# ProDocument_FAB-O-MATIC_2024-05-19.net
KiCad netlist of a schematic drawn in EasyEDA Pro
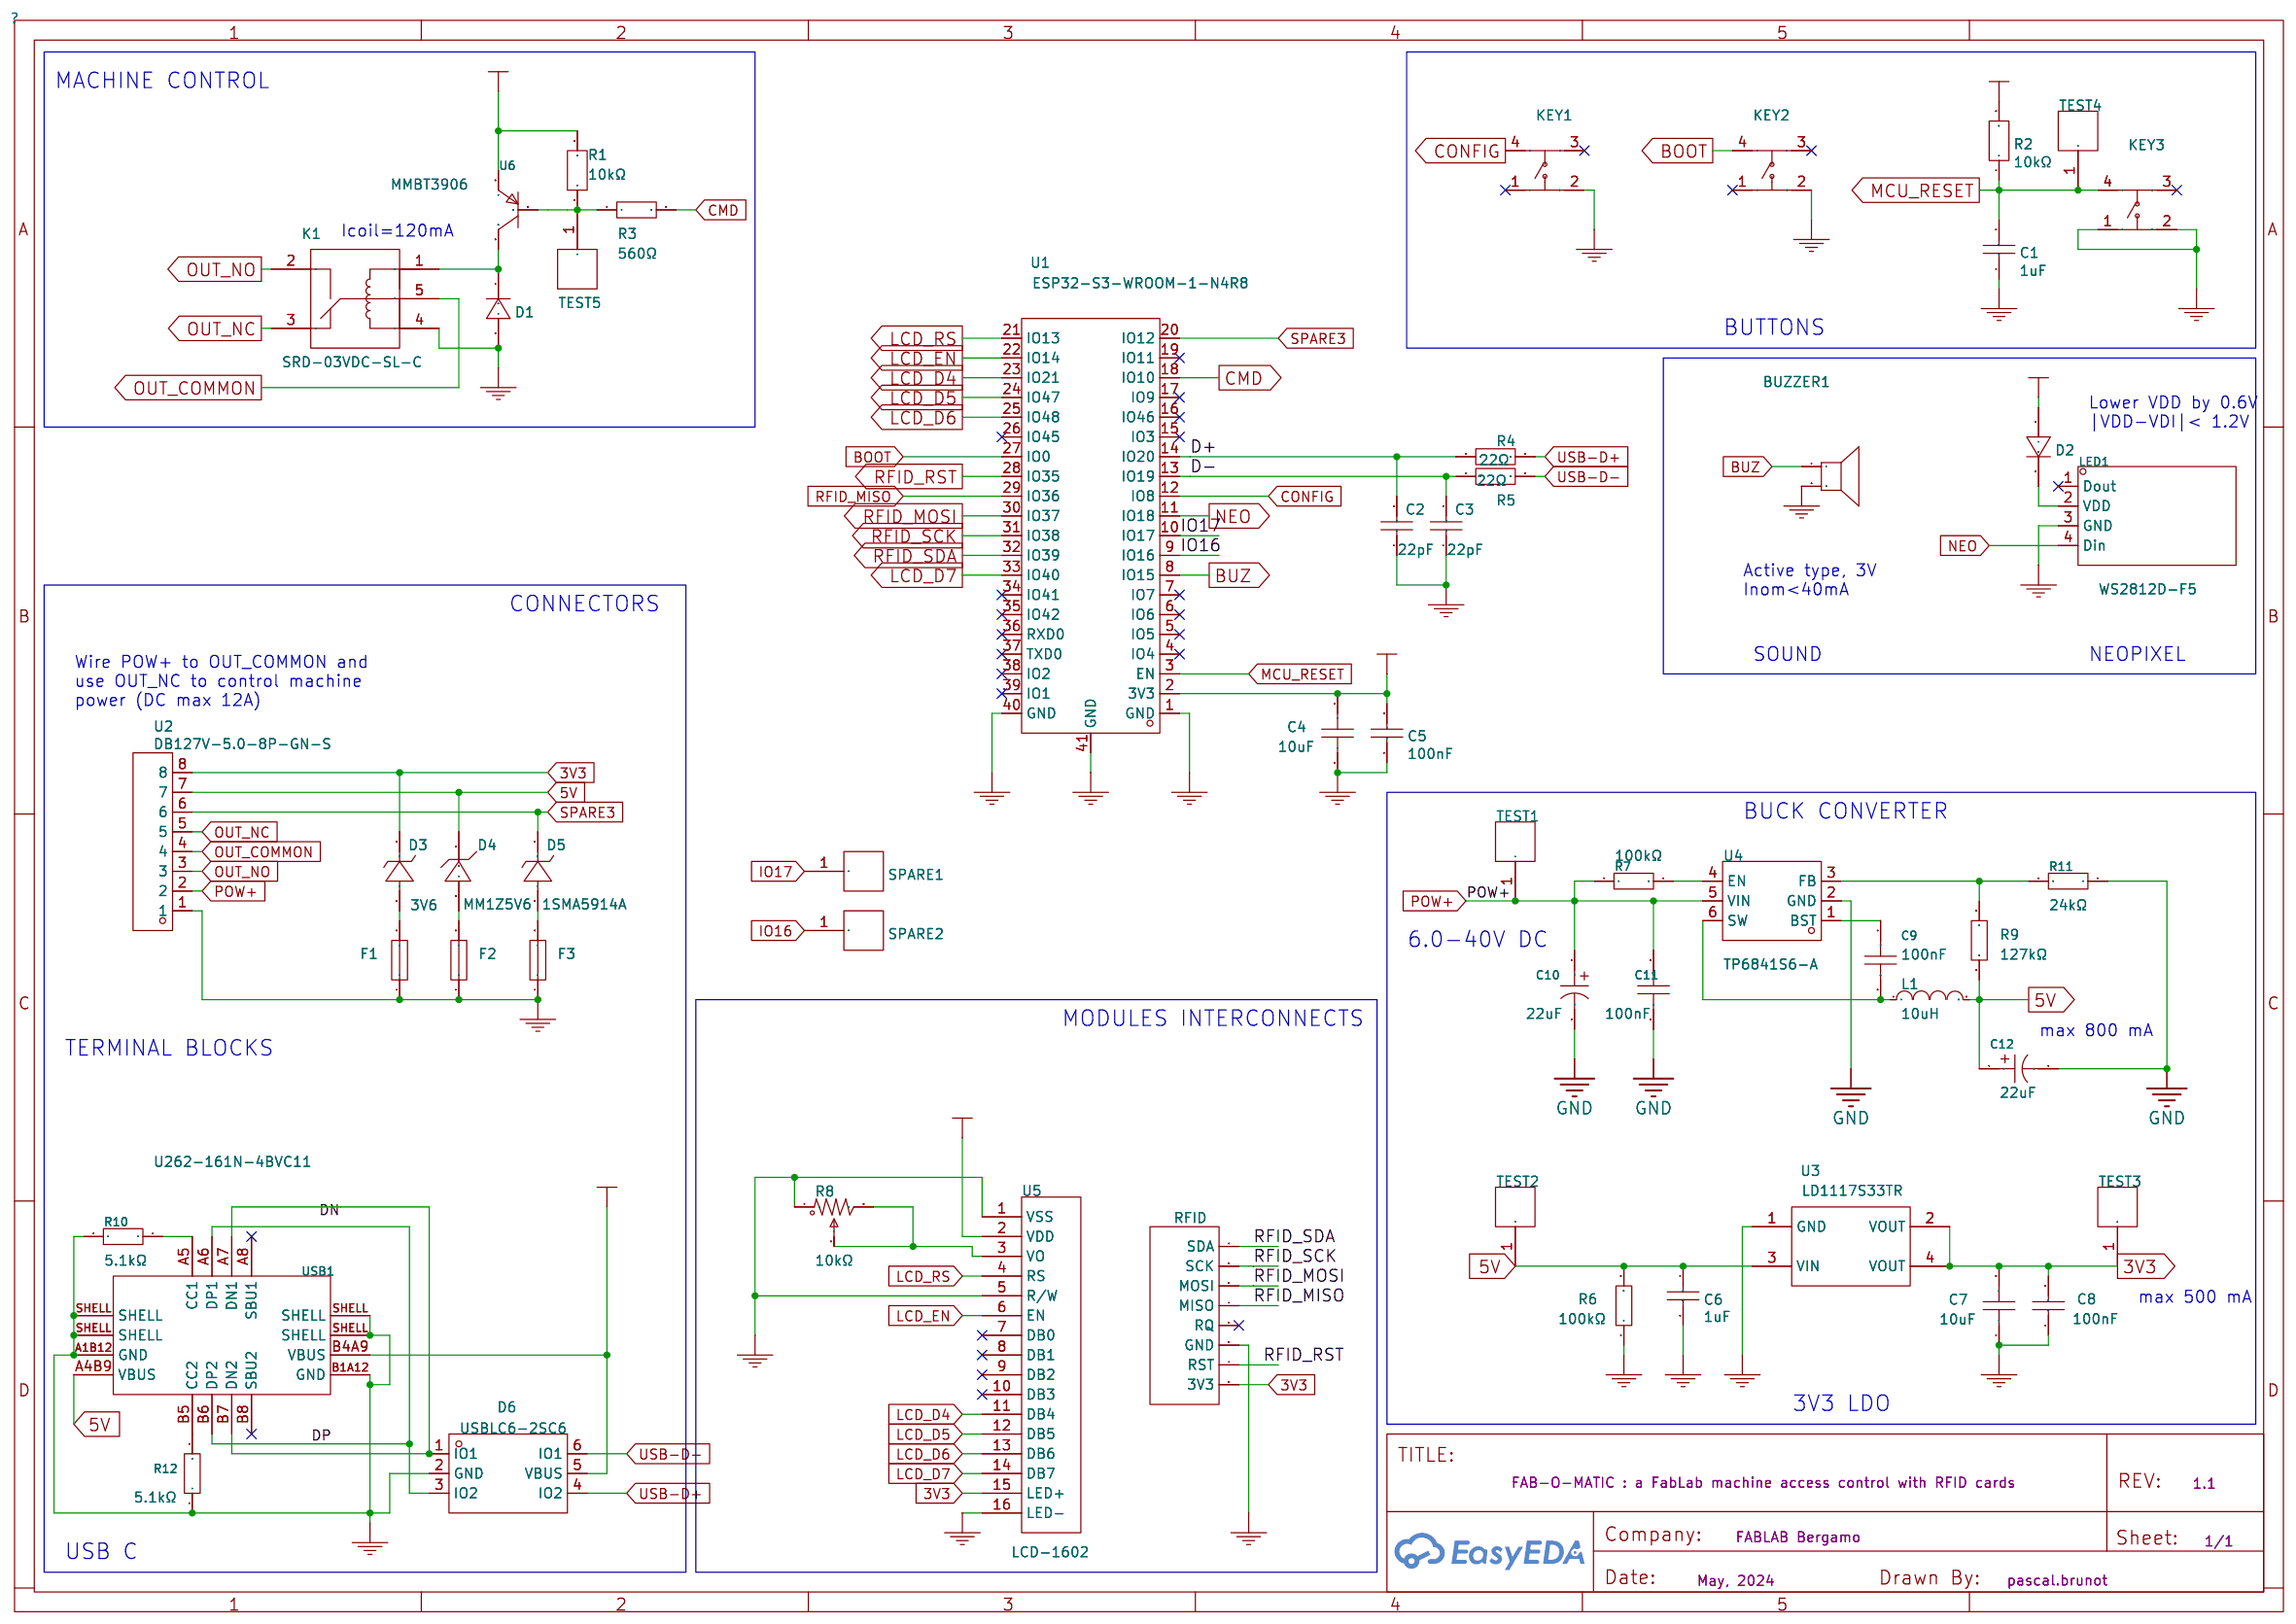
[diagram p0: Schematics]
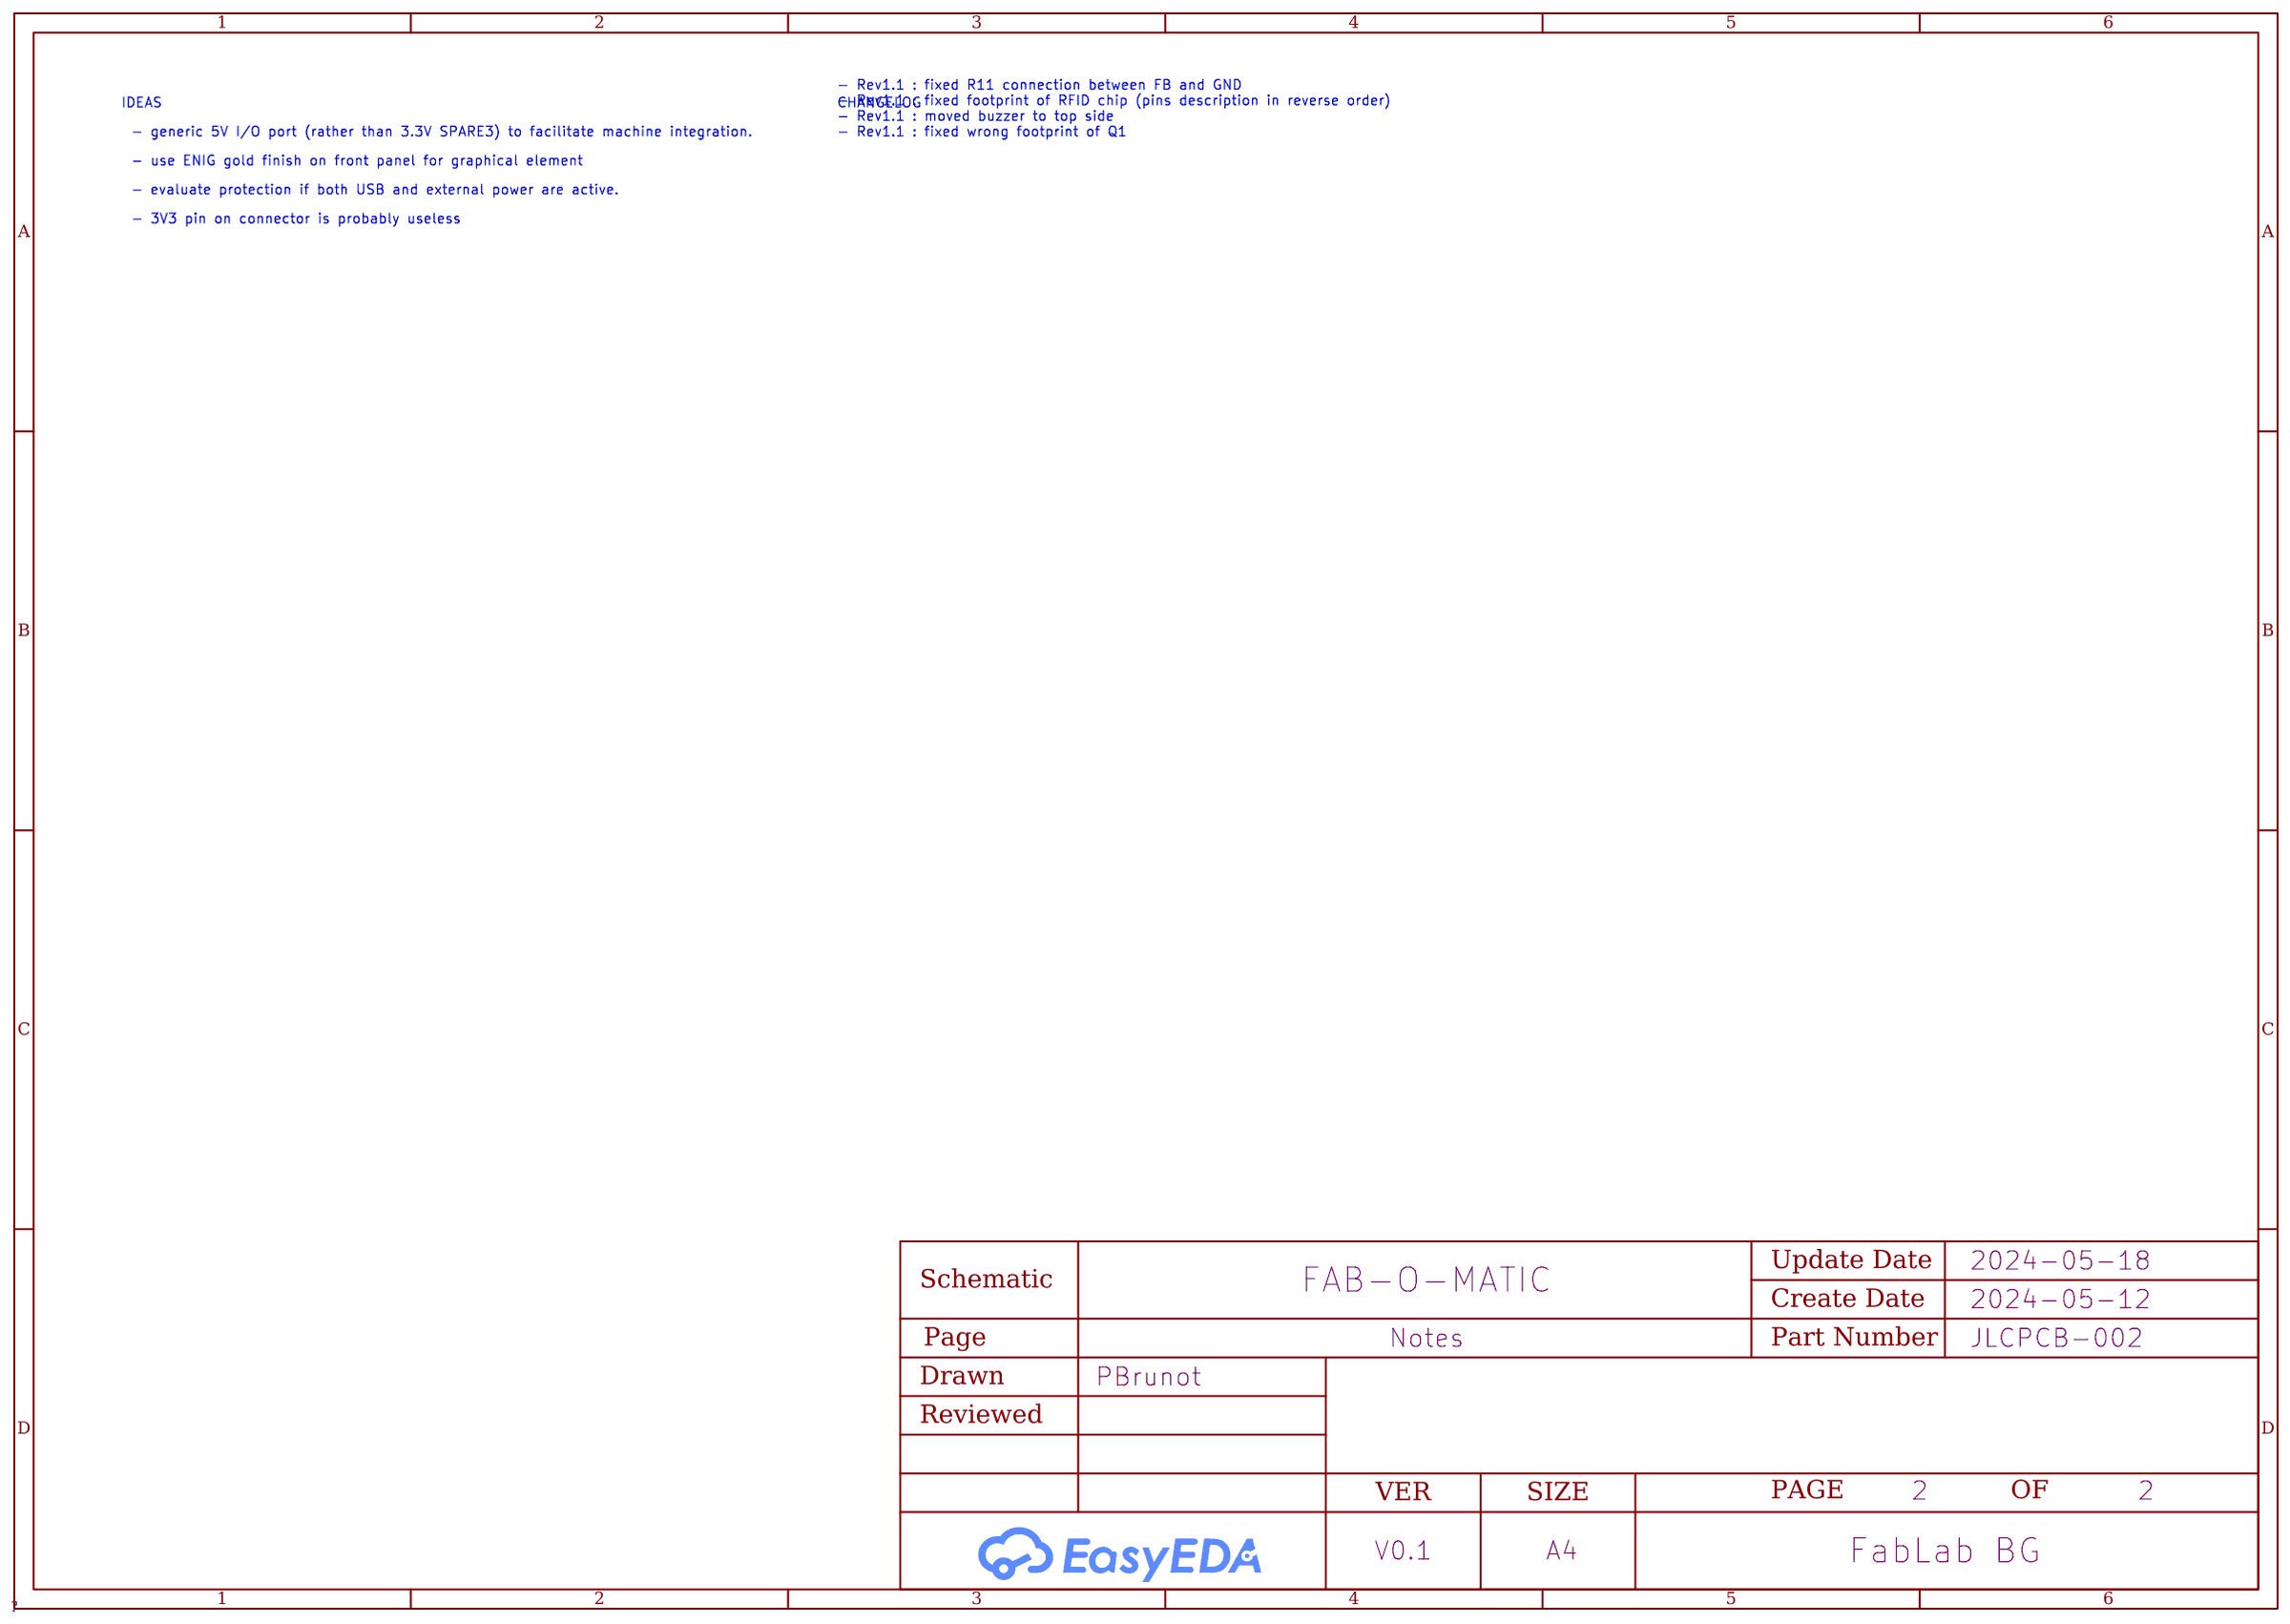
[diagram p1: Notes]

(export (version "E")
  (design (tool "Eeschema 10.0.6"))
  (components
    (comp (ref "BUZZER1")
      (value "4kHz")
      (fields (field (name "Manufacturer Part") "SFN-12055PA6.5") (field (name "Manufacturer") "S&S(海旭)"))
      (libsource (lib "easyedapro") (part "4000Hz"))
    )
    (comp (ref "C1")
      (value "1uF")
      (fields
        (field (name "Manufacturer Part") "CL21B105KBFNNNE")
        (field (name "Manufacturer") "SAMSUNG(三星)")
      )
      (libsource (lib "easyedapro") (part "1uF"))
    )
    (comp (ref "C2")
      (value "22pF")
      (fields
        (field (name "Manufacturer Part") "CL10C220JB8NNNC")
        (field (name "Manufacturer") "SAMSUNG(三星)")
      )
      (libsource (lib "easyedapro") (part "22pF"))
    )
    (comp (ref "C3")
      (value "22pF")
      (fields
        (field (name "Manufacturer Part") "CL10C220JB8NNNC")
        (field (name "Manufacturer") "SAMSUNG(三星)")
      )
      (libsource (lib "easyedapro") (part "22pF"))
    )
    (comp (ref "C4")
      (value "10uF")
      (fields
        (field (name "Manufacturer Part") "GRM21BR61H106KE43L")
        (field (name "Manufacturer") "muRata(村田)")
      )
      (libsource (lib "easyedapro") (part "10uF"))
    )
    (comp (ref "C5")
      (value "100nF")
      (fields
        (field (name "Manufacturer Part") "CL21B104KCFNNNE")
        (field (name "Manufacturer") "SAMSUNG(三星)")
      )
      (libsource (lib "easyedapro") (part "100nF"))
    )
    (comp (ref "C6")
      (value "1uF")
      (fields
        (field (name "Manufacturer Part") "CL21B105KBFNNNE")
        (field (name "Manufacturer") "SAMSUNG(三星)")
      )
      (libsource (lib "easyedapro") (part "1uF"))
    )
    (comp (ref "C7")
      (value "10uF")
      (fields
        (field (name "Manufacturer Part") "GRM21BR61H106KE43L")
        (field (name "Manufacturer") "muRata(村田)")
      )
      (libsource (lib "easyedapro") (part "10uF"))
    )
    (comp (ref "C8")
      (value "100nF")
      (fields
        (field (name "Manufacturer Part") "CL21B104KCFNNNE")
        (field (name "Manufacturer") "SAMSUNG(三星)")
      )
      (libsource (lib "easyedapro") (part "100nF"))
    )
    (comp (ref "C9")
      (value "100nF")
      (footprint "easyedapro:C0603")
      (fields
        (field (name "Manufacturer Part") "CC0603KRX7R9BB104")
        (field (name "Manufacturer") "YAGEO(国巨)")
      )
      (libsource (lib "easyedapro") (part "CC0603KRX7R9BB104"))
    )
    (comp (ref "C10")
      (value "22uF")
      (footprint "easyedapro:CAP-SMD_BD6.3-L6.6-W6.6-FD")
      (fields
        (field (name "Manufacturer Part") "RVT22UF50V67RV0028")
        (field (name "Manufacturer") "KNSCHA(科尼盛)")
      )
      (libsource (lib "easyedapro") (part "RVT22UF50V67RV0028"))
    )
    (comp (ref "C11")
      (value "100nF")
      (footprint "easyedapro:C0603")
      (fields
        (field (name "Manufacturer Part") "CC0603KRX7R9BB104")
        (field (name "Manufacturer") "YAGEO(国巨)")
      )
      (libsource (lib "easyedapro") (part "CC0603KRX7R9BB104"))
    )
    (comp (ref "C12")
      (value "22uF")
      (footprint "easyedapro:CAP-SMD_BD6.3-L6.6-W6.6-FD")
      (fields
        (field (name "Manufacturer Part") "RVT22UF50V67RV0028")
        (field (name "Manufacturer") "KNSCHA(科尼盛)")
      )
      (libsource (lib "easyedapro") (part "RVT22UF50V67RV0028"))
    )
    (comp (ref "D1")
      (value "SM4007PL")
      (fields (field (name "Manufacturer") "MDD"))
      (libsource (lib "easyedapro") (part "SM4007PL"))
    )
    (comp (ref "D2")
      (value "SM4007PL")
      (fields (field (name "Manufacturer") "MDD"))
      (libsource (lib "easyedapro") (part "SM4007PL"))
    )
    (comp (ref "D3")
      (value "3V6")
      (fields (field (name "Manufacturer") "LGE(鲁光)"))
      (libsource (lib "easyedapro") (part "3V6"))
    )
    (comp (ref "D4")
      (value "MM1Z5V6")
      (fields (field (name "Manufacturer") "ST(先科)"))
      (libsource (lib "easyedapro") (part "5V6"))
    )
    (comp (ref "D5")
      (value "1SMA5914A")
      (fields (field (name "Manufacturer") "LGE(鲁光)"))
      (libsource (lib "easyedapro") (part "3V6"))
    )
    (comp (ref "D6")
      (value "USBLC6-2SC6")
      (fields (field (name "Manufacturer") "TECH PUBLIC(台舟)"))
      (libsource (lib "easyedapro") (part "USBLC6"))
    )
    (comp (ref "F1")
      (value "1206L016WR")
      (fields (field (name "Manufacturer") "Littelfuse(美国力特)"))
      (libsource (lib "easyedapro") (part "1206L016WR"))
    )
    (comp (ref "F2")
      (value "1206L016WR")
      (fields (field (name "Manufacturer") "Littelfuse(美国力特)"))
      (libsource (lib "easyedapro") (part "1206L016WR"))
    )
    (comp (ref "F3")
      (value "1206L016WR")
      (fields (field (name "Manufacturer") "Littelfuse(美国力特)"))
      (libsource (lib "easyedapro") (part "1206L016WR"))
    )
    (comp (ref "K1")
      (value "SRD-03VDC-SL-C")
      (fields (field (name "Manufacturer") "松乐"))
      (libsource (lib "easyedapro") (part "SRD-03VDC-SL-C_C496430"))
    )
    (comp (ref "KEY1")
      (value "TSA063G60-250")
      (footprint "easyedapro:KEY-SMD_4P-L6.1-W6.1-P4.50-LS9.0")
      (fields (field (name "Manufacturer") "BRIGHT(博瑞泰)"))
      (libsource (lib "easyedapro") (part "TSA063G60-250"))
    )
    (comp (ref "KEY2")
      (value "TSA063G60-250")
      (footprint "easyedapro:KEY-SMD_4P-L6.1-W6.1-P4.50-LS9.0")
      (fields (field (name "Manufacturer") "BRIGHT(博瑞泰)"))
      (libsource (lib "easyedapro") (part "TSA063G60-250"))
    )
    (comp (ref "KEY3")
      (value "TSA063G60-250")
      (footprint "easyedapro:KEY-SMD_4P-L6.1-W6.1-P4.50-LS9.0")
      (fields (field (name "Manufacturer") "BRIGHT(博瑞泰)"))
      (libsource (lib "easyedapro") (part "TSA063G60-250"))
    )
    (comp (ref "L1")
      (value "10uH")
      (footprint "easyedapro:IND-SMD_L4.0-W4.0")
      (fields (field (name "Manufacturer Part") "SWPA4030S100MT") (field (name "Manufacturer") "Sunlord(顺络)"))
      (libsource (lib "easyedapro") (part "SWPA4030S100MT"))
    )
    (comp (ref "LED1")
      (value "WS2812D-F5")
      (footprint "easyedapro:LED-TH_4P-BD5.8-P1.30")
      (description "Lamp Holder Type:5mm圆形灯头")
      (fields (field (name "Manufacturer") "worldsemi"))
      (libsource (lib "easyedapro") (part "WS2812D-F5"))
    )
    (comp (ref "P1")
      (value "RFID")
      (footprint "easyedapro:footprint_17af")
      (fields
        (field (name "Manufacturer Part") "Female headerHDR1X8-2.54")
        (field (name "Manufacturer") "BOOMELE")
      )
      (libsource (lib "easyedapro") (part "RFID"))
    )
    (comp (ref "R1")
      (value "10kΩ")
      (fields
        (field (name "Manufacturer Part") "0805W8F1002T5E")
        (field (name "Manufacturer") "UNI-ROYAL(厚声)")
      )
      (libsource (lib "easyedapro") (part "10k"))
    )
    (comp (ref "R2")
      (value "10kΩ")
      (fields
        (field (name "Manufacturer Part") "0805W8F1002T5E")
        (field (name "Manufacturer") "UNI-ROYAL(厚声)")
      )
      (libsource (lib "easyedapro") (part "10k"))
    )
    (comp (ref "R3")
      (value "560Ω")
      (fields
        (field (name "Manufacturer Part") "0805W8F5600T5E")
        (field (name "Manufacturer") "UNI-ROYAL(厚声)")
      )
      (libsource (lib "easyedapro") (part "560Ω"))
    )
    (comp (ref "R4")
      (value "22Ω")
      (fields
        (field (name "Manufacturer Part") "0603WAF220JT5E")
        (field (name "Manufacturer") "UNI-ROYAL(厚声)")
      )
      (libsource (lib "easyedapro") (part "22"))
    )
    (comp (ref "R5")
      (value "22Ω")
      (fields
        (field (name "Manufacturer Part") "0603WAF220JT5E")
        (field (name "Manufacturer") "UNI-ROYAL(厚声)")
      )
      (libsource (lib "easyedapro") (part "22"))
    )
    (comp (ref "R6")
      (value "100kΩ")
      (fields
        (field (name "Manufacturer Part") "0805W8F1003T5E")
        (field (name "Manufacturer") "UNI-ROYAL(厚声)")
      )
      (libsource (lib "easyedapro") (part "100kΩ"))
    )
    (comp (ref "R7")
      (value "100kΩ")
      (footprint "easyedapro:R0603")
      (fields
        (field (name "Manufacturer Part") "0603WAF1003T5E")
        (field (name "Manufacturer") "UNI-ROYAL(厚声)")
      )
      (libsource (lib "easyedapro") (part "0603WAF1003T5E"))
    )
    (comp (ref "R8")
      (value "10kΩ")
      (footprint "easyedapro:RES-ADJ-TH_3362P")
      (description "Resistance: Tolerance:±10% Tolerance:±10%")
      (fields (field (name "Manufacturer Part") "3362P-1-103") (field (name "Manufacturer") "BOCHEN(博晨)"))
      (libsource (lib "easyedapro") (part "3362P-1-103_C118956"))
    )
    (comp (ref "R9")
      (value "127kΩ")
      (footprint "easyedapro:R0603")
      (fields (field (name "Manufacturer Part") "RC0603FR-07127KL") (field (name "Manufacturer") "YAGEO(国巨)"))
      (libsource (lib "easyedapro") (part "RC0603FR-07127KL"))
    )
    (comp (ref "R10")
      (value "5.1kΩ")
      (footprint "easyedapro:R0603")
      (fields
        (field (name "Manufacturer Part") "0603WAF5101T5E")
        (field (name "Manufacturer") "UNI-ROYAL(厚声)")
      )
      (libsource (lib "easyedapro") (part "0603WAF5101T5E"))
    )
    (comp (ref "R11")
      (value "24kΩ")
      (footprint "easyedapro:R0603")
      (fields
        (field (name "Manufacturer Part") "0603WAF2402T5E")
        (field (name "Manufacturer") "UNI-ROYAL(厚声)")
      )
      (libsource (lib "easyedapro") (part "0603WAF2402T5E"))
    )
    (comp (ref "R12")
      (value "5.1kΩ")
      (footprint "easyedapro:R0603")
      (fields
        (field (name "Manufacturer Part") "0603WAF5101T5E")
        (field (name "Manufacturer") "UNI-ROYAL(厚声)")
      )
      (libsource (lib "easyedapro") (part "0603WAF5101T5E"))
    )
    (comp (ref "SPARE1")
      (value "0577-0-43-80-21-27-10-0")
      (footprint "easyedapro:footprint_662d")
      (libsource (lib "easyedapro") (part "0577-0-43-80-21-27-10-0"))
    )
    (comp (ref "SPARE2")
      (value "0577-0-43-80-21-27-10-0")
      (footprint "easyedapro:footprint_662d")
      (libsource (lib "easyedapro") (part "0577-0-43-80-21-27-10-0"))
    )
    (comp (ref "TEST1")
      (value "0577-0-43-80-21-27-10-0")
      (footprint "easyedapro:footprint_662d")
      (libsource (lib "easyedapro") (part "0577-0-43-80-21-27-10-0"))
    )
    (comp (ref "TEST2")
      (value "0577-0-43-80-21-27-10-0")
      (footprint "easyedapro:footprint_662d")
      (libsource (lib "easyedapro") (part "0577-0-43-80-21-27-10-0"))
    )
    (comp (ref "TEST3")
      (value "0577-0-43-80-21-27-10-0")
      (footprint "easyedapro:footprint_662d")
      (libsource (lib "easyedapro") (part "0577-0-43-80-21-27-10-0"))
    )
    (comp (ref "TEST4")
      (value "0577-0-43-80-21-27-10-0")
      (footprint "easyedapro:footprint_662d")
      (libsource (lib "easyedapro") (part "0577-0-43-80-21-27-10-0"))
    )
    (comp (ref "TEST5")
      (value "0577-0-43-80-21-27-10-0")
      (footprint "easyedapro:footprint_662d")
      (libsource (lib "easyedapro") (part "0577-0-43-80-21-27-10-0"))
    )
    (comp (ref "U1")
      (value "ESP32-S3-WROOM-1-N4R8")
      (fields (field (name "Manufacturer") "ESPRESSIF(乐鑫)"))
      (libsource (lib "easyedapro") (part "ESP32-S3-WROOM-1-N4"))
    )
    (comp (ref "U2")
      (value "DB127V-5.0-8P-GN-S")
      (fields (field (name "Manufacturer") "DORABO(地博电气)"))
      (libsource (lib "easyedapro") (part "DB127V-5.0-8P-GN-S"))
    )
    (comp (ref "U3")
      (value "LD1117S33TR")
      (fields (field (name "Manufacturer") "ST(意法半导体)"))
      (libsource (lib "easyedapro") (part "LD1117S33TR"))
    )
    (comp (ref "U4")
      (value "TP6841S6-A")
      (footprint "easyedapro:SOT-23-6_L2.9-W1.6-P0.95-LS2.8-BL")
      (fields (field (name "Manufacturer") "TECH PUBLIC(台舟)"))
      (libsource (lib "easyedapro") (part "TP6841S6-A"))
    )
    (comp (ref "U5")
      (value "LCD-1602")
      (footprint "easyedapro:footprint_8a57")
      (fields (field (name "Manufacturer Part") "?"))
      (libsource (lib "easyedapro") (part "LCD-1602"))
    )
    (comp (ref "U6")
      (value "MMBT3906")
      (footprint "easyedapro:SOT-23-3_L2.9-W1.3-P1.90-LS2.4-BR")
      (fields (field (name "Manufacturer") "宏迦橙"))
      (libsource (lib "easyedapro") (part "MMBT3906_C7420354"))
    )
    (comp (ref "USB1")
      (value "U262-161N-4BVC11")
      (footprint "easyedapro:USB-3.1-SMD_U262-161N-4BVC11")
      (fields (field (name "Manufacturer") "XKB Connectivity(中国星坤)"))
      (libsource (lib "easyedapro") (part "U262-16XN-4BVC11"))
    )
  )
  (nets
    (net (code "1") (name "3V3") (class "Default")
      (node (ref "C4") (pin "2") (pinfunction "2_2") (pintype "unspecified"))
      (node (ref "C5") (pin "2") (pinfunction "2_2") (pintype "input"))
      (node (ref "C7") (pin "2") (pinfunction "2_2") (pintype "unspecified"))
      (node (ref "C8") (pin "2") (pinfunction "2_2") (pintype "input"))
      (node (ref "D3") (pin "1") (pinfunction "C_1") (pintype "unspecified"))
      (node (ref "P1") (pin "8") (pinfunction "3V3_8") (pintype "input"))
      (node (ref "R1") (pin "2") (pinfunction "2_2") (pintype "unspecified"))
      (node (ref "R2") (pin "2") (pinfunction "2_2") (pintype "unspecified"))
      (node (ref "TEST3") (pin "1") (pinfunction "1_1") (pintype "unspecified"))
      (node (ref "U1") (pin "2") (pinfunction "3V3_2") (pintype "unspecified"))
      (node (ref "U2") (pin "8") (pinfunction "8_8") (pintype "unspecified"))
      (node (ref "U3") (pin "2") (pinfunction "VOUT_2") (pintype "unspecified"))
      (node (ref "U3") (pin "4") (pinfunction "VOUT_4") (pintype "unspecified"))
      (node (ref "U5") (pin "15") (pinfunction "LED+_15") (pintype "unspecified"))
      (node (ref "U6") (pin "2") (pinfunction "E_2") (pintype "input"))
    )
    (net (code "2") (name "5V") (class "Default")
      (node (ref "C12") (pin "1") (pinfunction "1_1") (pintype "input"))
      (node (ref "C6") (pin "1") (pinfunction "1_1") (pintype "input"))
      (node (ref "D2") (pin "2") (pinfunction "A_2") (pintype "unspecified"))
      (node (ref "D4") (pin "1") (pinfunction "C_1") (pintype "unspecified"))
      (node (ref "D6") (pin "5") (pinfunction "VBUS_5") (pintype "unspecified"))
      (node (ref "L1") (pin "2") (pinfunction "2_2") (pintype "input"))
      (node (ref "R6") (pin "2") (pinfunction "2_2") (pintype "unspecified"))
      (node (ref "R9") (pin "1") (pinfunction "1_1") (pintype "unspecified"))
      (node (ref "TEST2") (pin "1") (pinfunction "1_1") (pintype "unspecified"))
      (node (ref "U2") (pin "7") (pinfunction "7_7") (pintype "unspecified"))
      (node (ref "U3") (pin "3") (pinfunction "VIN_3") (pintype "unspecified"))
      (node (ref "U5") (pin "2") (pinfunction "VDD_2") (pintype "unspecified"))
      (node (ref "USB1") (pin "A4B9") (pinfunction "VBUS_A4B9") (pintype "input"))
      (node (ref "USB1") (pin "B4A9") (pinfunction "VBUS_B4A9") (pintype "input"))
    )
    (net (code "3") (name "BOOT") (class "Default")
      (node (ref "KEY2") (pin "4") (pinfunction "4_4") (pintype "input"))
      (node (ref "U1") (pin "27") (pinfunction "IO0_27") (pintype "unspecified"))
    )
    (net (code "4") (name "BUZ") (class "Default")
      (node (ref "BUZZER1") (pin "1") (pinfunction "1_1") (pintype "unspecified"))
      (node (ref "U1") (pin "8") (pinfunction "IO15_8") (pintype "unspecified"))
    )
    (net (code "5") (name "CMD") (class "Default")
      (node (ref "R3") (pin "2") (pinfunction "2_2") (pintype "input"))
      (node (ref "U1") (pin "18") (pinfunction "IO10_18") (pintype "unspecified"))
    )
    (net (code "6") (name "CONFIG") (class "Default")
      (node (ref "KEY1") (pin "4") (pinfunction "4_4") (pintype "input"))
      (node (ref "U1") (pin "12") (pinfunction "IO8_12") (pintype "unspecified"))
    )
    (net (code "7") (name "D+") (class "Default")
      (node (ref "C2") (pin "2") (pinfunction "2_2") (pintype "input"))
      (node (ref "R4") (pin "1") (pinfunction "1_1") (pintype "input"))
      (node (ref "U1") (pin "14") (pinfunction "IO20_14") (pintype "unspecified"))
    )
    (net (code "8") (name "D-") (class "Default")
      (node (ref "C3") (pin "2") (pinfunction "2_2") (pintype "input"))
      (node (ref "R5") (pin "1") (pinfunction "1_1") (pintype "input"))
      (node (ref "U1") (pin "13") (pinfunction "IO19_13") (pintype "unspecified"))
    )
    (net (code "9") (name "DN") (class "Default")
      (node (ref "D6") (pin "1") (pinfunction "IO1_1") (pintype "unspecified"))
      (node (ref "USB1") (pin "A7") (pinfunction "DN1_A7") (pintype "input"))
      (node (ref "USB1") (pin "B7") (pinfunction "DN2_B7") (pintype "input"))
    )
    (net (code "10") (name "DP") (class "Default")
      (node (ref "D6") (pin "3") (pinfunction "IO2_3") (pintype "unspecified"))
      (node (ref "USB1") (pin "A6") (pinfunction "DP1_A6") (pintype "input"))
      (node (ref "USB1") (pin "B6") (pinfunction "DP2_B6") (pintype "input"))
    )
    (net (code "11") (name "GND") (class "Default")
      (node (ref "BUZZER1") (pin "2") (pinfunction "2_2") (pintype "unspecified"))
      (node (ref "C1") (pin "1") (pinfunction "1_1") (pintype "input"))
      (node (ref "C10") (pin "2") (pinfunction "2_2") (pintype "input"))
      (node (ref "C11") (pin "1") (pinfunction "1_1") (pintype "input"))
      (node (ref "C12") (pin "2") (pinfunction "2_2") (pintype "input"))
      (node (ref "C2") (pin "1") (pinfunction "1_1") (pintype "input"))
      (node (ref "C3") (pin "1") (pinfunction "1_1") (pintype "input"))
      (node (ref "C4") (pin "1") (pinfunction "1_1") (pintype "unspecified"))
      (node (ref "C5") (pin "1") (pinfunction "1_1") (pintype "input"))
      (node (ref "C6") (pin "2") (pinfunction "2_2") (pintype "input"))
      (node (ref "C7") (pin "1") (pinfunction "1_1") (pintype "unspecified"))
      (node (ref "C8") (pin "1") (pinfunction "1_1") (pintype "input"))
      (node (ref "D1") (pin "2") (pinfunction "A_2") (pintype "unspecified"))
      (node (ref "D6") (pin "2") (pinfunction "GND_2") (pintype "unspecified"))
      (node (ref "F1") (pin "1") (pinfunction "1_1") (pintype "unspecified"))
      (node (ref "F2") (pin "1") (pinfunction "1_1") (pintype "unspecified"))
      (node (ref "F3") (pin "1") (pinfunction "1_1") (pintype "unspecified"))
      (node (ref "K1") (pin "4") (pinfunction "4_4") (pintype "unspecified"))
      (node (ref "KEY1") (pin "2") (pinfunction "2_2") (pintype "input"))
      (node (ref "KEY2") (pin "2") (pinfunction "2_2") (pintype "input"))
      (node (ref "KEY3") (pin "1") (pinfunction "1_1") (pintype "input"))
      (node (ref "KEY3") (pin "2") (pinfunction "2_2") (pintype "input"))
      (node (ref "LED1") (pin "3") (pinfunction "GND_3") (pintype "input"))
      (node (ref "P1") (pin "6") (pinfunction "GND_6") (pintype "input"))
      (node (ref "R10") (pin "2") (pinfunction "2_2") (pintype "input"))
      (node (ref "R11") (pin "1") (pinfunction "1_1") (pintype "input"))
      (node (ref "R12") (pin "1") (pinfunction "1_1") (pintype "input"))
      (node (ref "R6") (pin "1") (pinfunction "1_1") (pintype "unspecified"))
      (node (ref "R8") (pin "1") (pinfunction "1_1") (pintype "input"))
      (node (ref "U1") (pin "1") (pinfunction "GND_1") (pintype "unspecified"))
      (node (ref "U1") (pin "40") (pinfunction "GND_40") (pintype "unspecified"))
      (node (ref "U1") (pin "41") (pinfunction "GND_41") (pintype "unspecified"))
      (node (ref "U2") (pin "1") (pinfunction "1_1") (pintype "unspecified"))
      (node (ref "U3") (pin "1") (pinfunction "GND_1") (pintype "unspecified"))
      (node (ref "U4") (pin "2") (pinfunction "GND_2") (pintype "input"))
      (node (ref "U5") (pin "1") (pinfunction "VSS_1") (pintype "unspecified"))
      (node (ref "U5") (pin "16") (pinfunction "LED-_16") (pintype "unspecified"))
      (node (ref "U5") (pin "5") (pinfunction "R/W_5") (pintype "unspecified"))
      (node (ref "USB1") (pin "A1B12") (pinfunction "GND_A1B12") (pintype "input"))
      (node (ref "USB1") (pin "B1A12") (pinfunction "GND_B1A12") (pintype "input"))
      (node (ref "USB1") (pin "SHELL") (pinfunction "SHELL_SHELL") (pintype "input"))
    )
    (net (code "12") (name "IO16") (class "Default")
      (node (ref "SPARE2") (pin "1") (pinfunction "1_1") (pintype "unspecified"))
      (node (ref "U1") (pin "9") (pinfunction "IO16_9") (pintype "unspecified"))
    )
    (net (code "13") (name "IO17") (class "Default")
      (node (ref "SPARE1") (pin "1") (pinfunction "1_1") (pintype "unspecified"))
      (node (ref "U1") (pin "10") (pinfunction "IO17_10") (pintype "unspecified"))
    )
    (net (code "14") (name "LCD_D4") (class "Default")
      (node (ref "U1") (pin "23") (pinfunction "IO21_23") (pintype "unspecified"))
      (node (ref "U5") (pin "11") (pinfunction "DB4_11") (pintype "unspecified"))
    )
    (net (code "15") (name "LCD_D5") (class "Default")
      (node (ref "U1") (pin "24") (pinfunction "IO47_24") (pintype "unspecified"))
      (node (ref "U5") (pin "12") (pinfunction "DB5_12") (pintype "unspecified"))
    )
    (net (code "16") (name "LCD_D6") (class "Default")
      (node (ref "U1") (pin "25") (pinfunction "IO48_25") (pintype "unspecified"))
      (node (ref "U5") (pin "13") (pinfunction "DB6_13") (pintype "unspecified"))
    )
    (net (code "17") (name "LCD_D7") (class "Default")
      (node (ref "U1") (pin "33") (pinfunction "IO40_33") (pintype "unspecified"))
      (node (ref "U5") (pin "14") (pinfunction "DB7_14") (pintype "unspecified"))
    )
    (net (code "18") (name "LCD_EN") (class "Default")
      (node (ref "U1") (pin "22") (pinfunction "IO14_22") (pintype "unspecified"))
      (node (ref "U5") (pin "6") (pinfunction "EN_6") (pintype "unspecified"))
    )
    (net (code "19") (name "LCD_RS") (class "Default")
      (node (ref "U1") (pin "21") (pinfunction "IO13_21") (pintype "unspecified"))
      (node (ref "U5") (pin "4") (pinfunction "RS_4") (pintype "unspecified"))
    )
    (net (code "20") (name "MCU_RESET") (class "Default")
      (node (ref "C1") (pin "2") (pinfunction "2_2") (pintype "input"))
      (node (ref "KEY3") (pin "4") (pinfunction "4_4") (pintype "input"))
      (node (ref "R2") (pin "1") (pinfunction "1_1") (pintype "unspecified"))
      (node (ref "TEST4") (pin "1") (pinfunction "1_1") (pintype "unspecified"))
      (node (ref "U1") (pin "3") (pinfunction "EN_3") (pintype "unspecified"))
    )
    (net (code "21") (name "NEO") (class "Default")
      (node (ref "LED1") (pin "4") (pinfunction "Din_4") (pintype "input"))
      (node (ref "U1") (pin "11") (pinfunction "IO18_11") (pintype "unspecified"))
    )
    (net (code "22") (name "Net-(D1-C)") (class "Default")
      (node (ref "D1") (pin "1") (pinfunction "C_1") (pintype "unspecified"))
      (node (ref "K1") (pin "1") (pinfunction "1_1") (pintype "unspecified"))
      (node (ref "U6") (pin "3") (pinfunction "C_3") (pintype "input"))
    )
    (net (code "23") (name "Net-(D2-C)") (class "Default")
      (node (ref "D2") (pin "1") (pinfunction "C_1") (pintype "unspecified"))
      (node (ref "LED1") (pin "2") (pinfunction "VDD_2") (pintype "input"))
    )
    (net (code "24") (name "Net-(D3-A)") (class "Default")
      (node (ref "D3") (pin "2") (pinfunction "A_2") (pintype "unspecified"))
      (node (ref "F1") (pin "2") (pinfunction "2_2") (pintype "unspecified"))
    )
    (net (code "25") (name "Net-(D4-A)") (class "Default")
      (node (ref "D4") (pin "2") (pinfunction "A_2") (pintype "unspecified"))
      (node (ref "F2") (pin "2") (pinfunction "2_2") (pintype "unspecified"))
    )
    (net (code "26") (name "Net-(D5-A)") (class "Default")
      (node (ref "D5") (pin "2") (pinfunction "A_2") (pintype "unspecified"))
      (node (ref "F3") (pin "2") (pinfunction "2_2") (pintype "unspecified"))
    )
    (net (code "27") (name "Net-(U4-BST)") (class "Default")
      (node (ref "C9") (pin "1") (pinfunction "1_1") (pintype "input"))
      (node (ref "U4") (pin "1") (pinfunction "BST_1") (pintype "input"))
    )
    (net (code "28") (name "Net-(U4-EN)") (class "Default")
      (node (ref "R7") (pin "2") (pinfunction "2_2") (pintype "input"))
      (node (ref "U4") (pin "4") (pinfunction "EN_4") (pintype "input"))
    )
    (net (code "29") (name "Net-(U4-FB)") (class "Default")
      (node (ref "R11") (pin "2") (pinfunction "2_2") (pintype "input"))
      (node (ref "R9") (pin "2") (pinfunction "2_2") (pintype "unspecified"))
      (node (ref "U4") (pin "3") (pinfunction "FB_3") (pintype "input"))
    )
    (net (code "30") (name "Net-(U4-SW)") (class "Default")
      (node (ref "C9") (pin "2") (pinfunction "2_2") (pintype "input"))
      (node (ref "L1") (pin "1") (pinfunction "1_1") (pintype "input"))
      (node (ref "U4") (pin "6") (pinfunction "SW_6") (pintype "input"))
    )
    (net (code "31") (name "Net-(U5-VO)") (class "Default")
      (node (ref "R8") (pin "2") (pinfunction "2_2") (pintype "input"))
      (node (ref "R8") (pin "3") (pinfunction "3_3") (pintype "input"))
      (node (ref "U5") (pin "3") (pinfunction "VO_3") (pintype "unspecified"))
    )
    (net (code "32") (name "Net-(U6-B)") (class "Default")
      (node (ref "R1") (pin "1") (pinfunction "1_1") (pintype "unspecified"))
      (node (ref "R3") (pin "1") (pinfunction "1_1") (pintype "input"))
      (node (ref "TEST5") (pin "1") (pinfunction "1_1") (pintype "unspecified"))
      (node (ref "U6") (pin "1") (pinfunction "B_1") (pintype "input"))
    )
    (net (code "33") (name "Net-(USB1-CC1)") (class "Default")
      (node (ref "R10") (pin "1") (pinfunction "1_1") (pintype "input"))
      (node (ref "USB1") (pin "A5") (pinfunction "CC1_A5") (pintype "input"))
    )
    (net (code "34") (name "Net-(USB1-CC2)") (class "Default")
      (node (ref "R12") (pin "2") (pinfunction "2_2") (pintype "input"))
      (node (ref "USB1") (pin "B5") (pinfunction "CC2_B5") (pintype "input"))
    )
    (net (code "35") (name "OUT_COMMON") (class "Default")
      (node (ref "K1") (pin "5") (pinfunction "5_5") (pintype "unspecified"))
      (node (ref "U2") (pin "4") (pinfunction "4_4") (pintype "unspecified"))
    )
    (net (code "36") (name "OUT_NC") (class "Default")
      (node (ref "K1") (pin "3") (pinfunction "3_3") (pintype "unspecified"))
      (node (ref "U2") (pin "5") (pinfunction "5_5") (pintype "unspecified"))
    )
    (net (code "37") (name "OUT_NO") (class "Default")
      (node (ref "K1") (pin "2") (pinfunction "2_2") (pintype "unspecified"))
      (node (ref "U2") (pin "3") (pinfunction "3_3") (pintype "unspecified"))
    )
    (net (code "38") (name "POW+") (class "Default")
      (node (ref "C10") (pin "1") (pinfunction "1_1") (pintype "input"))
      (node (ref "C11") (pin "2") (pinfunction "2_2") (pintype "input"))
      (node (ref "R7") (pin "1") (pinfunction "1_1") (pintype "input"))
      (node (ref "TEST1") (pin "1") (pinfunction "1_1") (pintype "unspecified"))
      (node (ref "U2") (pin "2") (pinfunction "2_2") (pintype "unspecified"))
      (node (ref "U4") (pin "5") (pinfunction "VIN_5") (pintype "input"))
    )
    (net (code "39") (name "RFID_MISO") (class "Default")
      (node (ref "P1") (pin "4") (pinfunction "MISO_4") (pintype "input"))
      (node (ref "U1") (pin "29") (pinfunction "IO36_29") (pintype "unspecified"))
    )
    (net (code "40") (name "RFID_MOSI") (class "Default")
      (node (ref "P1") (pin "3") (pinfunction "MOSI_3") (pintype "input"))
      (node (ref "U1") (pin "30") (pinfunction "IO37_30") (pintype "unspecified"))
    )
    (net (code "41") (name "RFID_RST") (class "Default")
      (node (ref "P1") (pin "7") (pinfunction "RST_7") (pintype "input"))
      (node (ref "U1") (pin "28") (pinfunction "IO35_28") (pintype "unspecified"))
    )
    (net (code "42") (name "RFID_SCK") (class "Default")
      (node (ref "P1") (pin "2") (pinfunction "SCK_2") (pintype "input"))
      (node (ref "U1") (pin "31") (pinfunction "IO38_31") (pintype "unspecified"))
    )
    (net (code "43") (name "RFID_SDA") (class "Default")
      (node (ref "P1") (pin "1") (pinfunction "SDA_1") (pintype "input"))
      (node (ref "U1") (pin "32") (pinfunction "IO39_32") (pintype "unspecified"))
    )
    (net (code "44") (name "SPARE3") (class "Default")
      (node (ref "D5") (pin "1") (pinfunction "C_1") (pintype "unspecified"))
      (node (ref "U1") (pin "20") (pinfunction "IO12_20") (pintype "unspecified"))
      (node (ref "U2") (pin "6") (pinfunction "6_6") (pintype "unspecified"))
    )
    (net (code "45") (name "USB-D+") (class "Default")
      (node (ref "D6") (pin "4") (pinfunction "IO2_4") (pintype "unspecified"))
      (node (ref "R4") (pin "2") (pinfunction "2_2") (pintype "input"))
    )
    (net (code "46") (name "USB-D-") (class "Default")
      (node (ref "D6") (pin "6") (pinfunction "IO1_6") (pintype "unspecified"))
      (node (ref "R5") (pin "2") (pinfunction "2_2") (pintype "input"))
    )
    (net (code "47") (name "unconnected-(KEY1-Pad1)") (class "Default")
      (node (ref "KEY1") (pin "1") (pinfunction "1_1") (pintype "input+no_connect"))
    )
    (net (code "48") (name "unconnected-(KEY1-Pad3)") (class "Default")
      (node (ref "KEY1") (pin "3") (pinfunction "3_3") (pintype "input+no_connect"))
    )
    (net (code "49") (name "unconnected-(KEY2-Pad1)") (class "Default")
      (node (ref "KEY2") (pin "1") (pinfunction "1_1") (pintype "input+no_connect"))
    )
    (net (code "50") (name "unconnected-(KEY2-Pad3)") (class "Default")
      (node (ref "KEY2") (pin "3") (pinfunction "3_3") (pintype "input+no_connect"))
    )
    (net (code "51") (name "unconnected-(KEY3-Pad3)") (class "Default")
      (node (ref "KEY3") (pin "3") (pinfunction "3_3") (pintype "input+no_connect"))
    )
    (net (code "52") (name "unconnected-(LED1-Dout-Pad1)") (class "Default")
      (node (ref "LED1") (pin "1") (pinfunction "Dout_1") (pintype "input+no_connect"))
    )
    (net (code "53") (name "unconnected-(P1-RQ-Pad5)") (class "Default")
      (node (ref "P1") (pin "5") (pinfunction "RQ_5") (pintype "input+no_connect"))
    )
    (net (code "54") (name "unconnected-(U1-IO1-Pad39)") (class "Default")
      (node (ref "U1") (pin "39") (pinfunction "IO1_39") (pintype "unspecified+no_connect"))
    )
    (net (code "55") (name "unconnected-(U1-IO2-Pad38)") (class "Default")
      (node (ref "U1") (pin "38") (pinfunction "IO2_38") (pintype "unspecified+no_connect"))
    )
    (net (code "56") (name "unconnected-(U1-IO3-Pad15)") (class "Default")
      (node (ref "U1") (pin "15") (pinfunction "IO3_15") (pintype "unspecified+no_connect"))
    )
    (net (code "57") (name "unconnected-(U1-IO4-Pad4)") (class "Default")
      (node (ref "U1") (pin "4") (pinfunction "IO4_4") (pintype "unspecified+no_connect"))
    )
    (net (code "58") (name "unconnected-(U1-IO5-Pad5)") (class "Default")
      (node (ref "U1") (pin "5") (pinfunction "IO5_5") (pintype "unspecified+no_connect"))
    )
    (net (code "59") (name "unconnected-(U1-IO6-Pad6)") (class "Default")
      (node (ref "U1") (pin "6") (pinfunction "IO6_6") (pintype "unspecified+no_connect"))
    )
    (net (code "60") (name "unconnected-(U1-IO7-Pad7)") (class "Default")
      (node (ref "U1") (pin "7") (pinfunction "IO7_7") (pintype "unspecified+no_connect"))
    )
    (net (code "61") (name "unconnected-(U1-IO9-Pad17)") (class "Default")
      (node (ref "U1") (pin "17") (pinfunction "IO9_17") (pintype "unspecified+no_connect"))
    )
    (net (code "62") (name "unconnected-(U1-IO11-Pad19)") (class "Default")
      (node (ref "U1") (pin "19") (pinfunction "IO11_19") (pintype "unspecified+no_connect"))
    )
    (net (code "63") (name "unconnected-(U1-IO41-Pad34)") (class "Default")
      (node (ref "U1") (pin "34") (pinfunction "IO41_34") (pintype "unspecified+no_connect"))
    )
    (net (code "64") (name "unconnected-(U1-IO42-Pad35)") (class "Default")
      (node (ref "U1") (pin "35") (pinfunction "IO42_35") (pintype "unspecified+no_connect"))
    )
    (net (code "65") (name "unconnected-(U1-IO45-Pad26)") (class "Default")
      (node (ref "U1") (pin "26") (pinfunction "IO45_26") (pintype "unspecified+no_connect"))
    )
    (net (code "66") (name "unconnected-(U1-IO46-Pad16)") (class "Default")
      (node (ref "U1") (pin "16") (pinfunction "IO46_16") (pintype "unspecified+no_connect"))
    )
    (net (code "67") (name "unconnected-(U1-RXD0-Pad36)") (class "Default")
      (node (ref "U1") (pin "36") (pinfunction "RXD0_36") (pintype "unspecified+no_connect"))
    )
    (net (code "68") (name "unconnected-(U1-TXD0-Pad37)") (class "Default")
      (node (ref "U1") (pin "37") (pinfunction "TXD0_37") (pintype "unspecified+no_connect"))
    )
    (net (code "69") (name "unconnected-(U5-DB0-Pad7)") (class "Default")
      (node (ref "U5") (pin "7") (pinfunction "DB0_7") (pintype "unspecified+no_connect"))
    )
    (net (code "70") (name "unconnected-(U5-DB1-Pad8)") (class "Default")
      (node (ref "U5") (pin "8") (pinfunction "DB1_8") (pintype "unspecified+no_connect"))
    )
    (net (code "71") (name "unconnected-(U5-DB2-Pad9)") (class "Default")
      (node (ref "U5") (pin "9") (pinfunction "DB2_9") (pintype "unspecified+no_connect"))
    )
    (net (code "72") (name "unconnected-(U5-DB3-Pad10)") (class "Default")
      (node (ref "U5") (pin "10") (pinfunction "DB3_10") (pintype "unspecified+no_connect"))
    )
    (net (code "73") (name "unconnected-(USB1-SBU1-PadA8)") (class "Default")
      (node (ref "USB1") (pin "A8") (pinfunction "SBU1_A8") (pintype "input+no_connect"))
    )
    (net (code "74") (name "unconnected-(USB1-SBU2-PadB8)") (class "Default")
      (node (ref "USB1") (pin "B8") (pinfunction "SBU2_B8") (pintype "input+no_connect"))
    )
  )
)
